# Power_Supply.net
KiCad netlist of a schematic drawn in Altium Designer
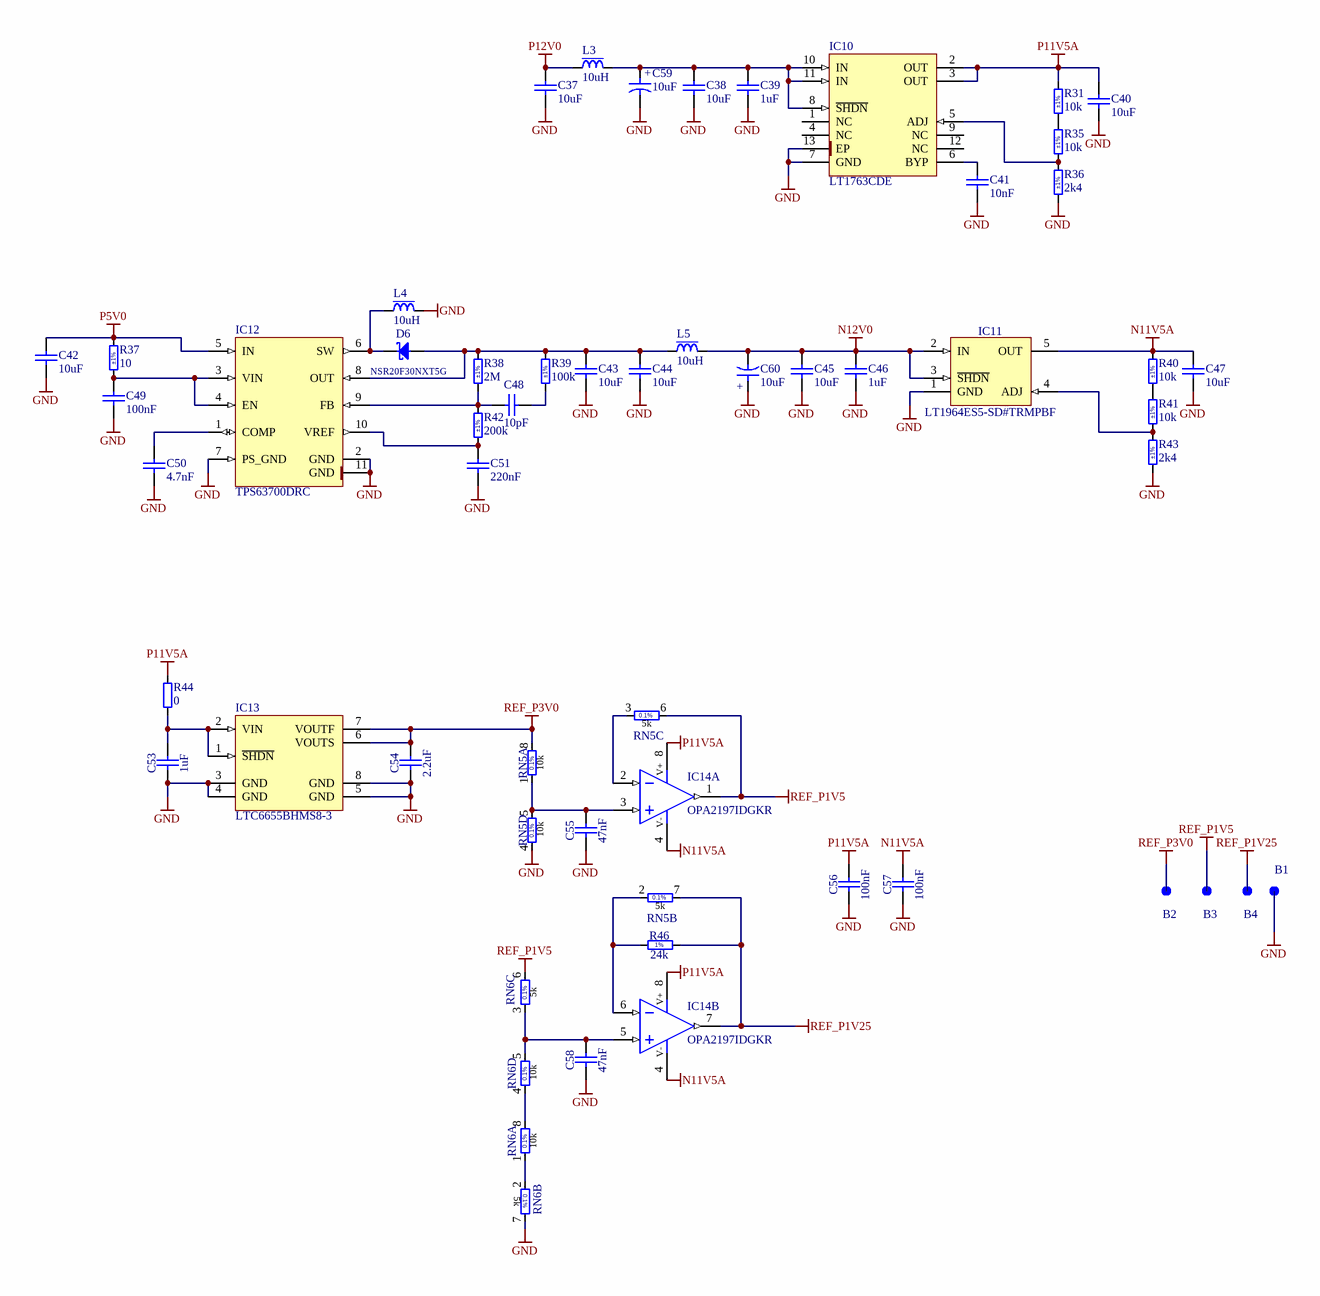
[diagram p0: Power_Supply.SchDoc]

(export (version "E")
  (design (tool "Eeschema 10.0.6"))
  (components
    (comp (ref "B1")
      (value "SMD Pad")
      (footprint "C100")
      (description "Pad")
      (fields (field (name "PART NUMBER") "SMD_PAD_D1MM") (field (name "AUTHOR") "CERN DEM JLC"))
      (libsource (lib "Eletro-mechanical") (part "Single SMD Pad (Round)"))
    )
    (comp (ref "B2")
      (value "SMD Pad")
      (footprint "C100")
      (description "Pad")
      (fields (field (name "PART NUMBER") "SMD_PAD_D1MM") (field (name "AUTHOR") "CERN DEM JLC"))
      (libsource (lib "Eletro-mechanical") (part "Single SMD Pad (Round)"))
    )
    (comp (ref "B3")
      (value "SMD Pad")
      (footprint "C100")
      (description "Pad")
      (fields (field (name "PART NUMBER") "SMD_PAD_D1MM") (field (name "AUTHOR") "CERN DEM JLC"))
      (libsource (lib "Eletro-mechanical") (part "Single SMD Pad (Round)"))
    )
    (comp (ref "B4")
      (value "SMD Pad")
      (footprint "C100")
      (description "Pad")
      (fields (field (name "PART NUMBER") "SMD_PAD_D1MM") (field (name "AUTHOR") "CERN DEM JLC"))
      (libsource (lib "Eletro-mechanical") (part "Single SMD Pad (Round)"))
    )
    (comp (ref "C37")
      (value "10uF")
      (footprint "CAPC1709X100N")
      (description "Non-polarised capacitor")
      (fields
        (field (name "PART NUMBER") "CC0603_10UF_25V_20%_X5R")
        (field (name "VOLTAGE") "25V")
        (field (name "AUTHOR") "CERN DEM BC")
      )
      (libsource (lib "Capacitors") (part "Capacitor - non polarized"))
    )
    (comp (ref "C38")
      (value "10uF")
      (footprint "CAPC1709X100N")
      (description "Non-polarised capacitor")
      (fields
        (field (name "PART NUMBER") "CC0603_10UF_25V_20%_X5R")
        (field (name "VOLTAGE") "25V")
        (field (name "AUTHOR") "CERN DEM BC")
      )
      (libsource (lib "Capacitors") (part "Capacitor - non polarized"))
    )
    (comp (ref "C39")
      (value "1uF")
      (footprint "CAPC1608X87N")
      (description "Non-polarised capacitor")
      (fields
        (field (name "PART NUMBER") "CC0603_1UF_25V_10%_X7R")
        (field (name "VOLTAGE") "25V")
        (field (name "AUTHOR") "CERN DEM JLC")
      )
      (libsource (lib "Capacitors") (part "Capacitor - non polarized"))
    )
    (comp (ref "C40")
      (value "10uF")
      (footprint "CAPC1709X100N")
      (description "Non-polarised capacitor")
      (fields
        (field (name "PART NUMBER") "CC0603_10UF_25V_20%_X5R")
        (field (name "VOLTAGE") "25V")
        (field (name "AUTHOR") "CERN DEM BC")
      )
      (libsource (lib "Capacitors") (part "Capacitor - non polarized"))
    )
    (comp (ref "C41")
      (value "10nF")
      (footprint "CAPC1005X55N")
      (description "Non-polarised capacitor")
      (fields
        (field (name "PART NUMBER") "CC0402_10NF_50V_5%_X7R")
        (field (name "VOLTAGE") "50V")
        (field (name "AUTHOR") "CERN DEM BC")
      )
      (libsource (lib "Capacitors") (part "Capacitor - non polarized"))
    )
    (comp (ref "C42")
      (value "10uF")
      (footprint "CAPC1709X100N")
      (description "Non-polarised capacitor")
      (fields
        (field (name "PART NUMBER") "CC0603_10UF_25V_20%_X5R")
        (field (name "VOLTAGE") "25V")
        (field (name "AUTHOR") "CERN DEM BC")
      )
      (libsource (lib "Capacitors") (part "Capacitor - non polarized"))
    )
    (comp (ref "C43")
      (value "10uF")
      (footprint "CAPC1709X100N")
      (description "Non-polarised capacitor")
      (fields
        (field (name "PART NUMBER") "CC0603_10UF_25V_20%_X5R")
        (field (name "VOLTAGE") "25V")
        (field (name "AUTHOR") "CERN DEM BC")
      )
      (libsource (lib "Capacitors") (part "Capacitor - non polarized"))
    )
    (comp (ref "C44")
      (value "10uF")
      (footprint "CAPC1709X100N")
      (description "Non-polarised capacitor")
      (fields
        (field (name "PART NUMBER") "CC0603_10UF_25V_20%_X5R")
        (field (name "VOLTAGE") "25V")
        (field (name "AUTHOR") "CERN DEM BC")
      )
      (libsource (lib "Capacitors") (part "Capacitor - non polarized"))
    )
    (comp (ref "C45")
      (value "10uF")
      (footprint "CAPC1709X100N")
      (description "Non-polarised capacitor")
      (fields
        (field (name "PART NUMBER") "CC0603_10UF_25V_20%_X5R")
        (field (name "VOLTAGE") "25V")
        (field (name "AUTHOR") "CERN DEM BC")
      )
      (libsource (lib "Capacitors") (part "Capacitor - non polarized"))
    )
    (comp (ref "C46")
      (value "1uF")
      (footprint "CAPC1608X87N")
      (description "Non-polarised capacitor")
      (fields
        (field (name "PART NUMBER") "CC0603_1UF_25V_10%_X7R")
        (field (name "VOLTAGE") "25V")
        (field (name "AUTHOR") "CERN DEM JLC")
      )
      (libsource (lib "Capacitors") (part "Capacitor - non polarized"))
    )
    (comp (ref "C47")
      (value "10uF")
      (footprint "CAPC1709X100N")
      (description "Non-polarised capacitor")
      (fields
        (field (name "PART NUMBER") "CC0603_10UF_25V_20%_X5R")
        (field (name "VOLTAGE") "25V")
        (field (name "AUTHOR") "CERN DEM BC")
      )
      (libsource (lib "Capacitors") (part "Capacitor - non polarized"))
    )
    (comp (ref "C48")
      (value "10pF")
      (footprint "CAPC1005X55N")
      (description "Non-polarised capacitor")
      (fields
        (field (name "PART NUMBER") "CC0402_10PF_50V_5%_C0G")
        (field (name "VOLTAGE") "50V")
        (field (name "AUTHOR") "CERN DEM JLC")
      )
      (libsource (lib "Capacitors") (part "Capacitor - non polarized"))
    )
    (comp (ref "C49")
      (value "100nF")
      (footprint "CAPC1005X55N")
      (description "Non-polarised capacitor")
      (fields
        (field (name "PART NUMBER") "CC0402_100NF_50V_10%_X7R")
        (field (name "VOLTAGE") "50V")
        (field (name "AUTHOR") "CERN DEM MR")
      )
      (libsource (lib "Capacitors") (part "Capacitor - non polarized"))
    )
    (comp (ref "C50")
      (value "4.7nF")
      (footprint "CAPC1005X55N")
      (description "Non-polarised capacitor")
      (fields
        (field (name "PART NUMBER") "CC0402_4.7NF_16V_10%_X7R")
        (field (name "VOLTAGE") "16V")
        (field (name "AUTHOR") "CERN DEM JLC")
      )
      (libsource (lib "Capacitors") (part "Capacitor - non polarized"))
    )
    (comp (ref "C51")
      (value "220nF")
      (footprint "CAPC1005X55N")
      (description "Non-polarised capacitor")
      (fields
        (field (name "PART NUMBER") "CC0402_220NF_35V_10%_X7R")
        (field (name "VOLTAGE") "35V")
        (field (name "AUTHOR") "CERN DEM HF")
      )
      (libsource (lib "Capacitors") (part "Capacitor - non polarized"))
    )
    (comp (ref "C53")
      (value "1uF")
      (footprint "CAPC1608X87N")
      (description "Non-polarised capacitor")
      (fields
        (field (name "PART NUMBER") "CC0603_1UF_25V_10%_X7R")
        (field (name "VOLTAGE") "25V")
        (field (name "AUTHOR") "CERN DEM JLC")
      )
      (libsource (lib "Capacitors") (part "Capacitor - non polarized"))
    )
    (comp (ref "C54")
      (value "2.2uF")
      (footprint "CAPC1608X87N")
      (description "Non-polarised capacitor")
      (fields
        (field (name "PART NUMBER") "CC0603_2.2UF_16V_10%_X5R")
        (field (name "VOLTAGE") "16V")
        (field (name "AUTHOR") "CERN DEM JLC")
      )
      (libsource (lib "Capacitors") (part "Capacitor - non polarized"))
    )
    (comp (ref "C55")
      (value "47nF")
      (footprint "CAPC2012X135N")
      (description "Non-polarised capacitor")
      (fields
        (field (name "PART NUMBER") "CC0805_47NF_25V_5%_C0G")
        (field (name "VOLTAGE") "25V")
        (field (name "AUTHOR") "CERN DEM JLC")
      )
      (libsource (lib "Capacitors") (part "Capacitor - non polarized"))
    )
    (comp (ref "C56")
      (value "100nF")
      (footprint "CAPC1005X55N")
      (description "Non-polarised capacitor")
      (fields
        (field (name "PART NUMBER") "CC0402_100NF_16V_10%_X5R")
        (field (name "VOLTAGE") "16V")
        (field (name "AUTHOR") "CERN DEM JLC")
      )
      (libsource (lib "Capacitors") (part "Capacitor - non polarized"))
    )
    (comp (ref "C57")
      (value "100nF")
      (footprint "CAPC1005X55N")
      (description "Non-polarised capacitor")
      (fields
        (field (name "PART NUMBER") "CC0402_100NF_16V_10%_X5R")
        (field (name "VOLTAGE") "16V")
        (field (name "AUTHOR") "CERN DEM JLC")
      )
      (libsource (lib "Capacitors") (part "Capacitor - non polarized"))
    )
    (comp (ref "C58")
      (value "47nF")
      (footprint "CAPC2012X135N")
      (description "Non-polarised capacitor")
      (fields
        (field (name "PART NUMBER") "CC0805_47NF_25V_5%_C0G")
        (field (name "VOLTAGE") "25V")
        (field (name "AUTHOR") "CERN DEM JLC")
      )
      (libsource (lib "Capacitors") (part "Capacitor - non polarized"))
    )
    (comp (ref "C59")
      (value "10uF")
      (footprint "CAPMP3216X180N")
      (description "Polarised capacitor")
      (fields
        (field (name "PART NUMBER") "CTE3216-18_10UF_16V_20%_AVX_TCJ")
        (field (name "VOLTAGE") "16V")
        (field (name "AUTHOR") "CERN DEM JLC")
      )
      (libsource (lib "Capacitors") (part "Capacitor - polarized"))
    )
    (comp (ref "C60")
      (value "10uF")
      (footprint "CAPMP3216X180N")
      (description "Polarised capacitor")
      (fields
        (field (name "PART NUMBER") "CTE3216-18_10UF_16V_20%_AVX_TCJ")
        (field (name "VOLTAGE") "16V")
        (field (name "AUTHOR") "CERN DEM JLC")
      )
      (libsource (lib "Capacitors") (part "Capacitor - polarized"))
    )
    (comp (ref "D6")
      (value "NSR20F30NXT5G")
      (footprint "DSN2")
      (description "Schottky Diode")
      (fields
        (field (name "MANUFACTURER") "onsemi")
        (field (name "ARENA PART NUMBER") "140-000035")
        (field (name "AUTHOR") "Michal Beldyga")
      )
      (libsource (lib "Semiconductors") (part "Diode Schottky"))
    )
    (comp (ref "IC10")
      (value "LT1763CDE")
      (footprint "SON50P300X400X80-13N-R180X340")
      (description "1.22V to 20V 500mA, Low Noise, LDO Adjustable Micropower Regulator")
      (fields (field (name "MANUFACTURER") "LINEAR TECHNOLOGY") (field (name "AUTHOR") "CERN DEM HF"))
      (libsource (lib "ICs And Semiconductors") (part "LT1763xDE_a"))
    )
    (comp (ref "IC11")
      (value "LT1964ES5-SD#TRMPBF")
      (footprint "SOT95P280X100-5N")
      (description "200mA, Low Noise, Low Dropout Negative Micropower Regulator")
      (fields (field (name "MANUFACTURER") "LINEAR TECHNOLOGY") (field (name "AUTHOR") "CERN DEM JLC"))
      (libsource (lib "ICs And Semiconductors") (part "LT1964-SD"))
    )
    (comp (ref "IC12")
      (value "TPS63700DRC")
      (footprint "TEXAS_DRC (S-PVSON-N10)")
      (description "DC-DC Inverter")
      (fields (field (name "MANUFACTURER") "TEXAS INSTRUMENTS") (field (name "AUTHOR") "CERN DEM BC"))
      (libsource (lib "ICs And Semiconductors") (part "TPS63700DRC"))
    )
    (comp (ref "IC13")
      (value "LTC6655BHMS8-3")
      (footprint "SOP65P490X110-8N")
      (description "0.25ppm Noise, Low Drift Precision Buffered Voltage Reference")
      (fields (field (name "MANUFACTURER") "ANALOG DEVICES") (field (name "AUTHOR") "CERN DEM HF"))
      (libsource (lib "ICs And Semiconductors") (part "LTC6655"))
    )
    (comp (ref "IC14")
      (value "OPA2197IDGKR")
      (footprint "SOP65P490X110-8N")
      (description "36-V, Precision, Rail-to-Rail Input Output, Low Offset Voltage Op Amp 8-VSSOP")
      (fields (field (name "MANUFACTURER") "TEXAS INSTRUMENTS") (field (name "AUTHOR") "GK"))
      (libsource (lib "LIBRARY_SCH") (part "OA_OPA2197IDGKR"))
    )
    (comp (ref "L3")
      (value "10uH")
      (footprint "IND_WURTH_WE-TPC-2828")
      (description "Inductor With Core")
      (fields
        (field (name "PART NUMBER") "IND_10UH_20%_WURTH_WE-TPC_744025100")
        (field (name "POWER") "1A")
        (field (name "AUTHOR") "CERN DEM BC")
      )
      (libsource (lib "Inductors & Transformers") (part "Inductor With Magnetic core"))
    )
    (comp (ref "L4")
      (value "10uH")
      (footprint "IND_WURTH_WE-TPC-2828")
      (description "Inductor With Core")
      (fields
        (field (name "PART NUMBER") "IND_10UH_20%_WURTH_WE-TPC_744025100")
        (field (name "POWER") "1A")
        (field (name "AUTHOR") "CERN DEM BC")
      )
      (libsource (lib "Inductors & Transformers") (part "Inductor With Magnetic core"))
    )
    (comp (ref "L5")
      (value "10uH")
      (footprint "IND_WURTH_WE-TPC-2828")
      (description "Inductor With Core")
      (fields
        (field (name "PART NUMBER") "IND_10UH_20%_WURTH_WE-TPC_744025100")
        (field (name "POWER") "1A")
        (field (name "AUTHOR") "CERN DEM BC")
      )
      (libsource (lib "Inductors & Transformers") (part "Inductor With Magnetic core"))
    )
    (comp (ref "R31")
      (value "10k")
      (footprint "RESC1005X40N")
      (description "Resistor - 1%")
      (fields
        (field (name "TOLERANCE") "±1%")
        (field (name "PART NUMBER") "R0402_10K_1%_0.0625W_100PPM")
        (field (name "POWER") "0.0625W")
        (field (name "AUTHOR") "CERN DEM JLC")
      )
      (libsource (lib "Resistors") (part "Resistor - 1%"))
    )
    (comp (ref "R35")
      (value "10k")
      (footprint "RESC1005X40N")
      (description "Resistor - 1%")
      (fields
        (field (name "TOLERANCE") "±1%")
        (field (name "PART NUMBER") "R0402_10K_1%_0.0625W_100PPM")
        (field (name "POWER") "0.0625W")
        (field (name "AUTHOR") "CERN DEM JLC")
      )
      (libsource (lib "Resistors") (part "Resistor - 1%"))
    )
    (comp (ref "R36")
      (value "2k4")
      (footprint "RESC1005X40N")
      (description "Resistor - 1%")
      (fields
        (field (name "TOLERANCE") "±1%")
        (field (name "PART NUMBER") "R0402_2K4_1%_0.0625W_100PPM")
        (field (name "POWER") "0.0625W")
        (field (name "AUTHOR") "CERN DEM JLC")
      )
      (libsource (lib "Resistors") (part "Resistor - 1%"))
    )
    (comp (ref "R37")
      (value "10")
      (footprint "RESC1005X40N")
      (description "Resistor - 1%")
      (fields
        (field (name "TOLERANCE") "±1%")
        (field (name "PART NUMBER") "R0402_10R_1%_0.0625W_200PPM")
        (field (name "POWER") "0.0625W")
        (field (name "AUTHOR") "CERN DEM JLC")
      )
      (libsource (lib "Resistors") (part "Resistor - 1%"))
    )
    (comp (ref "R38")
      (value "2M")
      (footprint "RESC1005X40N")
      (description "Resistor - 1%")
      (fields
        (field (name "TOLERANCE") "±1%")
        (field (name "PART NUMBER") "R0402_2M_1%_0.0625W_100PPM")
        (field (name "POWER") "0.0625W")
        (field (name "AUTHOR") "CERN DEM JLC")
      )
      (libsource (lib "Resistors") (part "Resistor - 1%"))
    )
    (comp (ref "R39")
      (value "100k")
      (footprint "RESC1005X40N")
      (description "Resistor - 1%")
      (fields
        (field (name "TOLERANCE") "±1%")
        (field (name "PART NUMBER") "R0402_100K_1%_0.0625W_100PPM")
        (field (name "POWER") "0.0625W")
        (field (name "AUTHOR") "CERN DEM JLC")
      )
      (libsource (lib "Resistors") (part "Resistor - 1%"))
    )
    (comp (ref "R40")
      (value "10k")
      (footprint "RESC1005X40N")
      (description "Resistor - 1%")
      (fields
        (field (name "TOLERANCE") "±1%")
        (field (name "PART NUMBER") "R0402_10K_1%_0.0625W_100PPM")
        (field (name "POWER") "0.0625W")
        (field (name "AUTHOR") "CERN DEM JLC")
      )
      (libsource (lib "Resistors") (part "Resistor - 1%"))
    )
    (comp (ref "R41")
      (value "10k")
      (footprint "RESC1005X40N")
      (description "Resistor - 1%")
      (fields
        (field (name "TOLERANCE") "±1%")
        (field (name "PART NUMBER") "R0402_10K_1%_0.0625W_100PPM")
        (field (name "POWER") "0.0625W")
        (field (name "AUTHOR") "CERN DEM JLC")
      )
      (libsource (lib "Resistors") (part "Resistor - 1%"))
    )
    (comp (ref "R42")
      (value "200k")
      (footprint "RESC1005X40N")
      (description "Resistor - 1%")
      (fields
        (field (name "TOLERANCE") "±1%")
        (field (name "PART NUMBER") "R0402_200K_1%_0.0625W_100PPM")
        (field (name "POWER") "0.0625W")
        (field (name "AUTHOR") "CERN DEM JLC")
      )
      (libsource (lib "Resistors") (part "Resistor - 1%"))
    )
    (comp (ref "R43")
      (value "2k4")
      (footprint "RESC1005X40N")
      (description "Resistor - 1%")
      (fields
        (field (name "TOLERANCE") "±1%")
        (field (name "PART NUMBER") "R0402_2K4_1%_0.0625W_100PPM")
        (field (name "POWER") "0.0625W")
        (field (name "AUTHOR") "CERN DEM JLC")
      )
      (libsource (lib "Resistors") (part "Resistor - 1%"))
    )
    (comp (ref "R44")
      (value "0")
      (footprint "RESC1005X40N")
      (description "Resistor")
      (fields
        (field (name "PART NUMBER") "R0402_0R_JUMPER")
        (field (name "MANUFACTURER") "GENERIC")
        (field (name "AUTHOR") "CERN DEM JLC")
      )
      (libsource (lib "Resistors") (part "Resistor"))
    )
    (comp (ref "R46")
      (value "24k")
      (footprint "RESC1608X55N")
      (description "Resistor - 1%")
      (fields
        (field (name "PART NUMBER") "R0603_24K_1%_0.1W_100PPM")
        (field (name "POWER") "0.1W")
        (field (name "AUTHOR") "CERN DEM JLC")
      )
      (libsource (lib "") (part "Resistor - 1%_1"))
    )
    (comp (ref "RN5")
      (value "10k 5K 5K 10K")
      (footprint "SOIC127P600X175-8N")
      (description "DIL8 Resistor Network 4 Resistors 10k-5k-5k-10k 0.1%")
      (fields
        (field (name "PART NUMBER") "RN_10K_5K_VISHAY_AORN2-1AT3")
        (field (name "POWER") "4x0.1W")
        (field (name "AUTHOR") "CERN DEM JLC")
      )
      (libsource (lib "Resistors") (part "RN DIL8_4xR_10k-5k-5k-10k_0.1%"))
    )
    (comp (ref "RN6")
      (value "10k 5K 5K 10K")
      (footprint "SOIC127P600X175-8N")
      (description "DIL8 Resistor Network 4 Resistors 10k-5k-5k-10k 0.1%")
      (fields
        (field (name "PART NUMBER") "RN_10K_5K_VISHAY_AORN2-1AT3")
        (field (name "POWER") "4x0.1W")
        (field (name "AUTHOR") "CERN DEM JLC")
      )
      (libsource (lib "Resistors") (part "RN DIL8_4xR_10k-5k-5k-10k_0.1%"))
    )
  )
  (nets
    (net (code "1") (name "GND") (class "Default")
      (node (ref "B1") (pin "1") (pinfunction "1_1") (pintype "bidirectional"))
      (node (ref "C37") (pin "1") (pinfunction "1_1") (pintype "passive"))
      (node (ref "C38") (pin "1") (pinfunction "1_1") (pintype "passive"))
      (node (ref "C39") (pin "1") (pinfunction "1_1") (pintype "passive"))
      (node (ref "C40") (pin "1") (pinfunction "1_1") (pintype "passive"))
      (node (ref "C41") (pin "1") (pinfunction "1_1") (pintype "passive"))
      (node (ref "C42") (pin "1") (pinfunction "1_1") (pintype "passive"))
      (node (ref "C43") (pin "1") (pinfunction "1_1") (pintype "passive"))
      (node (ref "C44") (pin "1") (pinfunction "1_1") (pintype "passive"))
      (node (ref "C45") (pin "1") (pinfunction "1_1") (pintype "passive"))
      (node (ref "C46") (pin "1") (pinfunction "1_1") (pintype "passive"))
      (node (ref "C47") (pin "1") (pinfunction "1_1") (pintype "passive"))
      (node (ref "C49") (pin "1") (pinfunction "1_1") (pintype "passive"))
      (node (ref "C50") (pin "1") (pinfunction "1_1") (pintype "passive"))
      (node (ref "C51") (pin "1") (pinfunction "1_1") (pintype "passive"))
      (node (ref "C53") (pin "1") (pinfunction "1_1") (pintype "passive"))
      (node (ref "C54") (pin "1") (pinfunction "1_1") (pintype "passive"))
      (node (ref "C55") (pin "1") (pinfunction "1_1") (pintype "passive"))
      (node (ref "C56") (pin "1") (pinfunction "1_1") (pintype "passive"))
      (node (ref "C57") (pin "1") (pinfunction "1_1") (pintype "passive"))
      (node (ref "C58") (pin "1") (pinfunction "1_1") (pintype "passive"))
      (node (ref "C59") (pin "2") (pinfunction "2_2") (pintype "passive"))
      (node (ref "C60") (pin "1") (pinfunction "1_1") (pintype "passive"))
      (node (ref "IC10") (pin "13") (pinfunction "EP_13") (pintype "power_in"))
      (node (ref "IC10") (pin "7") (pinfunction "GND_7") (pintype "power_in"))
      (node (ref "IC11") (pin "1") (pinfunction "GND_1") (pintype "power_in"))
      (node (ref "IC12") (pin "11") (pinfunction "GND_11") (pintype "power_in"))
      (node (ref "IC12") (pin "2") (pinfunction "GND_2") (pintype "power_in"))
      (node (ref "IC12") (pin "7") (pinfunction "PS_GND_7") (pintype "input"))
      (node (ref "IC13") (pin "3") (pinfunction "GND_3") (pintype "power_in"))
      (node (ref "IC13") (pin "4") (pinfunction "GND_4") (pintype "power_in"))
      (node (ref "IC13") (pin "5") (pinfunction "GND_5") (pintype "power_in"))
      (node (ref "IC13") (pin "8") (pinfunction "GND_8") (pintype "power_in"))
      (node (ref "L4") (pin "2") (pinfunction "2_2") (pintype "passive"))
      (node (ref "R36") (pin "1") (pinfunction "1_1") (pintype "passive"))
      (node (ref "R43") (pin "1") (pinfunction "1_1") (pintype "passive"))
      (node (ref "RN5") (pin "4") (pinfunction "4_4") (pintype "passive"))
      (node (ref "RN6") (pin "7") (pinfunction "7_7") (pintype "passive"))
    )
    (net (code "2") (name "N11V5A") (class "Default")
      (node (ref "C47") (pin "2") (pinfunction "2_2") (pintype "passive"))
      (node (ref "C57") (pin "2") (pinfunction "2_2") (pintype "passive"))
      (node (ref "IC11") (pin "5") (pinfunction "OUT_5") (pintype "power_in"))
      (node (ref "IC14") (pin "4") (pinfunction "V-_4") (pintype "power_in"))
      (node (ref "R40") (pin "2") (pinfunction "2_2") (pintype "passive"))
    )
    (net (code "3") (name "N12V0") (class "Default")
      (node (ref "C45") (pin "2") (pinfunction "2_2") (pintype "passive"))
      (node (ref "C46") (pin "2") (pinfunction "2_2") (pintype "passive"))
      (node (ref "C60") (pin "2") (pinfunction "2_2") (pintype "passive"))
      (node (ref "IC11") (pin "2") (pinfunction "IN_2") (pintype "input"))
      (node (ref "IC11") (pin "3") (pinfunction "~{SHDN}_3") (pintype "input"))
      (node (ref "L5") (pin "2") (pinfunction "2_2") (pintype "passive"))
    )
    (net (code "4") (name "Net-(C48-Pad2)") (class "Default")
      (node (ref "C48") (pin "2") (pinfunction "2_2") (pintype "passive"))
      (node (ref "R39") (pin "1") (pinfunction "1_1") (pintype "passive"))
    )
    (net (code "5") (name "Net-(D6-A)") (class "Default")
      (node (ref "C43") (pin "2") (pinfunction "2_2") (pintype "passive"))
      (node (ref "C44") (pin "2") (pinfunction "2_2") (pintype "passive"))
      (node (ref "D6") (pin "2") (pinfunction "A_2") (pintype "passive"))
      (node (ref "IC12") (pin "8") (pinfunction "OUT_8") (pintype "input"))
      (node (ref "L5") (pin "1") (pinfunction "1_1") (pintype "passive"))
      (node (ref "R38") (pin "1") (pinfunction "1_1") (pintype "passive"))
      (node (ref "R39") (pin "2") (pinfunction "2_2") (pintype "passive"))
    )
    (net (code "6") (name "Net-(D6-C)") (class "Default")
      (node (ref "D6") (pin "1") (pinfunction "C_1") (pintype "passive"))
      (node (ref "IC12") (pin "6") (pinfunction "SW_6") (pintype "output"))
      (node (ref "L4") (pin "1") (pinfunction "1_1") (pintype "passive"))
    )
    (net (code "7") (name "Net-(IC10-ADJ)") (class "Default")
      (node (ref "IC10") (pin "5") (pinfunction "ADJ_5") (pintype "input"))
      (node (ref "R35") (pin "1") (pinfunction "1_1") (pintype "passive"))
      (node (ref "R36") (pin "2") (pinfunction "2_2") (pintype "passive"))
    )
    (net (code "8") (name "Net-(IC10-BYP)") (class "Default")
      (node (ref "C41") (pin "2") (pinfunction "2_2") (pintype "passive"))
      (node (ref "IC10") (pin "6") (pinfunction "BYP_6") (pintype "passive"))
    )
    (net (code "9") (name "Net-(IC10-~{SHDN})") (class "Default")
      (node (ref "C38") (pin "2") (pinfunction "2_2") (pintype "passive"))
      (node (ref "C39") (pin "2") (pinfunction "2_2") (pintype "passive"))
      (node (ref "C59") (pin "1") (pinfunction "1_1") (pintype "passive"))
      (node (ref "IC10") (pin "10") (pinfunction "IN_10") (pintype "input"))
      (node (ref "IC10") (pin "11") (pinfunction "IN_11") (pintype "input"))
      (node (ref "IC10") (pin "8") (pinfunction "~{SHDN}_8") (pintype "input"))
      (node (ref "L3") (pin "2") (pinfunction "2_2") (pintype "passive"))
    )
    (net (code "10") (name "Net-(IC11-ADJ)") (class "Default")
      (node (ref "IC11") (pin "4") (pinfunction "ADJ_4") (pintype "input"))
      (node (ref "R41") (pin "1") (pinfunction "1_1") (pintype "passive"))
      (node (ref "R43") (pin "2") (pinfunction "2_2") (pintype "passive"))
    )
    (net (code "11") (name "Net-(IC12-COMP)") (class "Default")
      (node (ref "C50") (pin "2") (pinfunction "2_2") (pintype "passive"))
      (node (ref "IC12") (pin "1") (pinfunction "COMP_1") (pintype "bidirectional"))
    )
    (net (code "12") (name "Net-(IC12-EN)") (class "Default")
      (node (ref "C49") (pin "2") (pinfunction "2_2") (pintype "passive"))
      (node (ref "IC12") (pin "3") (pinfunction "VIN_3") (pintype "input"))
      (node (ref "IC12") (pin "4") (pinfunction "EN_4") (pintype "input"))
      (node (ref "R37") (pin "1") (pinfunction "1_1") (pintype "passive"))
    )
    (net (code "13") (name "Net-(IC12-FB)") (class "Default")
      (node (ref "C48") (pin "1") (pinfunction "1_1") (pintype "passive"))
      (node (ref "IC12") (pin "9") (pinfunction "FB_9") (pintype "input"))
      (node (ref "R38") (pin "2") (pinfunction "2_2") (pintype "passive"))
      (node (ref "R42") (pin "2") (pinfunction "2_2") (pintype "passive"))
    )
    (net (code "14") (name "Net-(IC12-VREF)") (class "Default")
      (node (ref "C51") (pin "2") (pinfunction "2_2") (pintype "passive"))
      (node (ref "IC12") (pin "10") (pinfunction "VREF_10") (pintype "output"))
      (node (ref "R42") (pin "1") (pinfunction "1_1") (pintype "passive"))
    )
    (net (code "15") (name "Net-(IC13-VIN)") (class "Default")
      (node (ref "C53") (pin "2") (pinfunction "2_2") (pintype "passive"))
      (node (ref "IC13") (pin "1") (pinfunction "~{SHDN}_1") (pintype "input"))
      (node (ref "IC13") (pin "2") (pinfunction "VIN_2") (pintype "input"))
      (node (ref "R44") (pin "2") (pinfunction "2_2") (pintype "passive"))
    )
    (net (code "16") (name "Net-(IC14A-IN+)") (class "Default")
      (node (ref "C55") (pin "2") (pinfunction "2_2") (pintype "passive"))
      (node (ref "IC14") (pin "3") (pinfunction "IN+_3") (pintype "input"))
      (node (ref "RN5") (pin "1") (pinfunction "1_1") (pintype "passive"))
      (node (ref "RN5") (pin "5") (pinfunction "5_5") (pintype "passive"))
    )
    (net (code "17") (name "Net-(IC14A-IN-)") (class "Default")
      (node (ref "IC14") (pin "2") (pinfunction "IN-_2") (pintype "input"))
      (node (ref "RN5") (pin "3") (pinfunction "3_3") (pintype "passive"))
    )
    (net (code "18") (name "Net-(IC14B-IN+)") (class "Default")
      (node (ref "C58") (pin "2") (pinfunction "2_2") (pintype "passive"))
      (node (ref "IC14") (pin "5") (pinfunction "IN+_5") (pintype "input"))
      (node (ref "RN6") (pin "3") (pinfunction "3_3") (pintype "passive"))
      (node (ref "RN6") (pin "5") (pinfunction "5_5") (pintype "passive"))
    )
    (net (code "19") (name "Net-(IC14B-IN-)") (class "Default")
      (node (ref "IC14") (pin "6") (pinfunction "IN-_6") (pintype "input"))
      (node (ref "R46") (pin "1") (pinfunction "1_1") (pintype "passive"))
      (node (ref "RN5") (pin "2") (pinfunction "2_2") (pintype "passive"))
    )
    (net (code "20") (name "Net-(R31-Pad1)") (class "Default")
      (node (ref "R31") (pin "1") (pinfunction "1_1") (pintype "passive"))
      (node (ref "R35") (pin "2") (pinfunction "2_2") (pintype "passive"))
    )
    (net (code "21") (name "Net-(R40-Pad1)") (class "Default")
      (node (ref "R40") (pin "1") (pinfunction "1_1") (pintype "passive"))
      (node (ref "R41") (pin "2") (pinfunction "2_2") (pintype "passive"))
    )
    (net (code "22") (name "Net-(RN6-Pad1)") (class "Default")
      (node (ref "RN6") (pin "1") (pinfunction "1_1") (pintype "passive"))
      (node (ref "RN6") (pin "2") (pinfunction "2_2") (pintype "passive"))
    )
    (net (code "23") (name "Net-(RN6-Pad4)") (class "Default")
      (node (ref "RN6") (pin "4") (pinfunction "4_4") (pintype "passive"))
      (node (ref "RN6") (pin "8") (pinfunction "8_8") (pintype "passive"))
    )
    (net (code "24") (name "P5V0") (class "Default")
      (node (ref "C42") (pin "2") (pinfunction "2_2") (pintype "passive"))
      (node (ref "IC12") (pin "5") (pinfunction "IN_5") (pintype "input"))
      (node (ref "R37") (pin "2") (pinfunction "2_2") (pintype "passive"))
    )
    (net (code "25") (name "P11V5A") (class "Default")
      (node (ref "C40") (pin "2") (pinfunction "2_2") (pintype "passive"))
      (node (ref "C56") (pin "2") (pinfunction "2_2") (pintype "passive"))
      (node (ref "IC10") (pin "2") (pinfunction "OUT_2") (pintype "power_in"))
      (node (ref "IC10") (pin "3") (pinfunction "OUT_3") (pintype "power_in"))
      (node (ref "IC14") (pin "8") (pinfunction "V+_8") (pintype "power_in"))
      (node (ref "R31") (pin "2") (pinfunction "2_2") (pintype "passive"))
      (node (ref "R44") (pin "1") (pinfunction "1_1") (pintype "passive"))
    )
    (net (code "26") (name "P12V0") (class "Default")
      (node (ref "C37") (pin "2") (pinfunction "2_2") (pintype "passive"))
      (node (ref "L3") (pin "1") (pinfunction "1_1") (pintype "passive"))
    )
    (net (code "27") (name "REF_P1V5") (class "Default")
      (node (ref "B3") (pin "1") (pinfunction "1_1") (pintype "bidirectional"))
      (node (ref "IC14") (pin "1") (pinfunction "OUT_1") (pintype "output"))
      (node (ref "RN5") (pin "6") (pinfunction "6_6") (pintype "passive"))
      (node (ref "RN6") (pin "6") (pinfunction "6_6") (pintype "passive"))
    )
    (net (code "28") (name "REF_P1V25") (class "Default")
      (node (ref "B4") (pin "1") (pinfunction "1_1") (pintype "bidirectional"))
      (node (ref "IC14") (pin "7") (pinfunction "OUT_7") (pintype "output"))
      (node (ref "R46") (pin "2") (pinfunction "2_2") (pintype "passive"))
      (node (ref "RN5") (pin "7") (pinfunction "7_7") (pintype "passive"))
    )
    (net (code "29") (name "REF_P3V0") (class "Default")
      (node (ref "B2") (pin "1") (pinfunction "1_1") (pintype "bidirectional"))
      (node (ref "C54") (pin "2") (pinfunction "2_2") (pintype "passive"))
      (node (ref "IC13") (pin "6") (pinfunction "VOUTS_6") (pintype "power_in"))
      (node (ref "IC13") (pin "7") (pinfunction "VOUTF_7") (pintype "power_in"))
      (node (ref "RN5") (pin "8") (pinfunction "8_8") (pintype "passive"))
    )
    (net (code "30") (name "unconnected-(IC10-NC-Pad1)") (class "Default")
      (node (ref "IC10") (pin "1") (pinfunction "NC_1") (pintype "passive"))
    )
    (net (code "31") (name "unconnected-(IC10-NC-Pad4)") (class "Default")
      (node (ref "IC10") (pin "4") (pinfunction "NC_4") (pintype "passive"))
    )
    (net (code "32") (name "unconnected-(IC10-NC-Pad9)") (class "Default")
      (node (ref "IC10") (pin "9") (pinfunction "NC_9") (pintype "passive"))
    )
    (net (code "33") (name "unconnected-(IC10-NC-Pad12)") (class "Default")
      (node (ref "IC10") (pin "12") (pinfunction "NC_12") (pintype "passive"))
    )
  )
)
